# Memory.net
KiCad netlist of a schematic drawn in Altium Designer
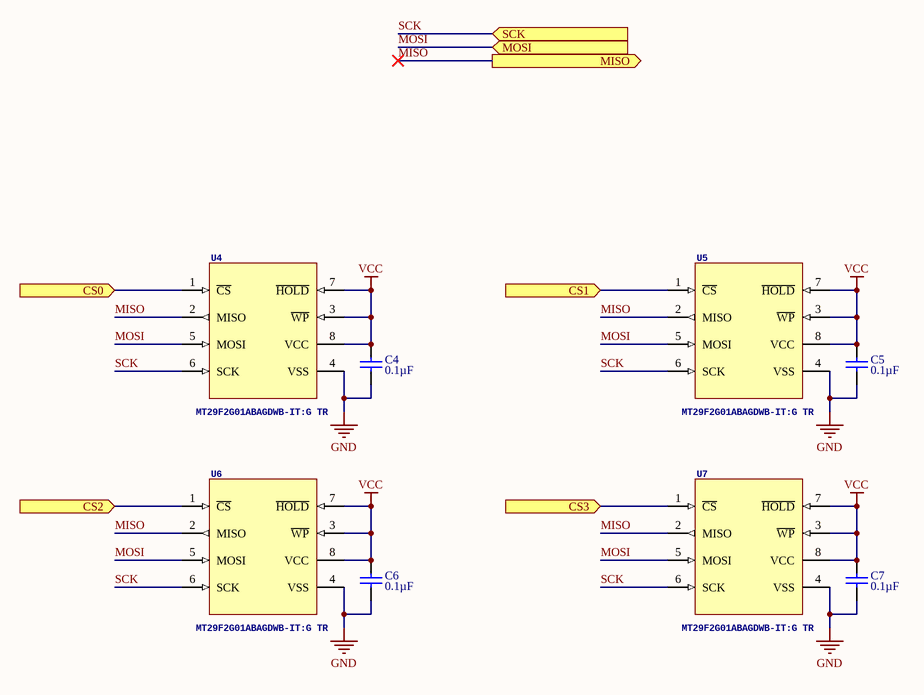
[diagram p0: Memory.SchDoc]

(export (version "E")
  (design (tool "Eeschema 10.0.6"))
  (components
    (comp (ref "C4")
      (value "CL10B104KO8NFNC")
      (footprint "C0603N")
      (fields
        (field (name "HOUSEPART") "NO")
        (field (name "TOLERANCE") "±10%")
        (field (name "VOLTAGE") "16V")
        (field (name "CAPACITANCE") "0.1µF")
      )
      (libsource (lib "MF_Passives") (part "CAPACITOR_NP"))
    )
    (comp (ref "C5")
      (value "CL10B104KO8NFNC")
      (footprint "C0603N")
      (fields
        (field (name "HOUSEPART") "NO")
        (field (name "TOLERANCE") "±10%")
        (field (name "VOLTAGE") "16V")
        (field (name "CAPACITANCE") "0.1µF")
      )
      (libsource (lib "MF_Passives") (part "CAPACITOR_NP"))
    )
    (comp (ref "C6")
      (value "CL10B104KO8NFNC")
      (footprint "C0603N")
      (fields
        (field (name "HOUSEPART") "NO")
        (field (name "TOLERANCE") "±10%")
        (field (name "VOLTAGE") "16V")
        (field (name "CAPACITANCE") "0.1µF")
      )
      (libsource (lib "MF_Passives") (part "CAPACITOR_NP"))
    )
    (comp (ref "C7")
      (value "CL10B104KO8NFNC")
      (footprint "C0603N")
      (fields
        (field (name "HOUSEPART") "NO")
        (field (name "TOLERANCE") "±10%")
        (field (name "VOLTAGE") "16V")
        (field (name "CAPACITANCE") "0.1µF")
      )
      (libsource (lib "MF_Passives") (part "CAPACITOR_NP"))
    )
    (comp (ref "U4")
      (value "MT29F2G01ABAGDWB-IT:G TR")
      (footprint "8-UDFN-MT29F")
      (description "IC Flash 2GB (UDFN8)")
      (libsource (lib "micron") (part "MT29F2G01ABAGDWB-IT{colon}G TR"))
    )
    (comp (ref "U5")
      (value "MT29F2G01ABAGDWB-IT:G TR")
      (footprint "8-UDFN-MT29F")
      (description "IC Flash 2GB (UDFN8)")
      (libsource (lib "micron") (part "MT29F2G01ABAGDWB-IT{colon}G TR"))
    )
    (comp (ref "U6")
      (value "MT29F2G01ABAGDWB-IT:G TR")
      (footprint "8-UDFN-MT29F")
      (description "IC Flash 2GB (UDFN8)")
      (libsource (lib "micron") (part "MT29F2G01ABAGDWB-IT{colon}G TR"))
    )
    (comp (ref "U7")
      (value "MT29F2G01ABAGDWB-IT:G TR")
      (footprint "8-UDFN-MT29F")
      (description "IC Flash 2GB (UDFN8)")
      (libsource (lib "micron") (part "MT29F2G01ABAGDWB-IT{colon}G TR"))
    )
  )
  (nets
    (net (code "1") (name "/CS0") (class "Default")
      (node (ref "U4") (pin "1") (pinfunction "~{CS}_1") (pintype "input"))
    )
    (net (code "2") (name "/CS1") (class "Default")
      (node (ref "U5") (pin "1") (pinfunction "~{CS}_1") (pintype "input"))
    )
    (net (code "3") (name "/CS2") (class "Default")
      (node (ref "U6") (pin "1") (pinfunction "~{CS}_1") (pintype "input"))
    )
    (net (code "4") (name "/CS3") (class "Default")
      (node (ref "U7") (pin "1") (pinfunction "~{CS}_1") (pintype "input"))
    )
    (net (code "5") (name "/MISO") (class "Default")
      (node (ref "U4") (pin "2") (pinfunction "MISO_2") (pintype "output"))
      (node (ref "U5") (pin "2") (pinfunction "MISO_2") (pintype "output"))
      (node (ref "U6") (pin "2") (pinfunction "MISO_2") (pintype "output"))
      (node (ref "U7") (pin "2") (pinfunction "MISO_2") (pintype "output"))
    )
    (net (code "6") (name "/MOSI") (class "Default")
      (node (ref "U4") (pin "5") (pinfunction "MOSI_5") (pintype "input"))
      (node (ref "U5") (pin "5") (pinfunction "MOSI_5") (pintype "input"))
      (node (ref "U6") (pin "5") (pinfunction "MOSI_5") (pintype "input"))
      (node (ref "U7") (pin "5") (pinfunction "MOSI_5") (pintype "input"))
    )
    (net (code "7") (name "/SCK") (class "Default")
      (node (ref "U4") (pin "6") (pinfunction "SCK_6") (pintype "input"))
      (node (ref "U5") (pin "6") (pinfunction "SCK_6") (pintype "input"))
      (node (ref "U6") (pin "6") (pinfunction "SCK_6") (pintype "input"))
      (node (ref "U7") (pin "6") (pinfunction "SCK_6") (pintype "input"))
    )
    (net (code "8") (name "GND") (class "Default")
      (node (ref "C4") (pin "2") (pinfunction "2_2") (pintype "passive"))
      (node (ref "C5") (pin "2") (pinfunction "2_2") (pintype "passive"))
      (node (ref "C6") (pin "2") (pinfunction "2_2") (pintype "passive"))
      (node (ref "C7") (pin "2") (pinfunction "2_2") (pintype "passive"))
      (node (ref "U4") (pin "4") (pinfunction "VSS_4") (pintype "power_in"))
      (node (ref "U5") (pin "4") (pinfunction "VSS_4") (pintype "power_in"))
      (node (ref "U6") (pin "4") (pinfunction "VSS_4") (pintype "power_in"))
      (node (ref "U7") (pin "4") (pinfunction "VSS_4") (pintype "power_in"))
    )
    (net (code "9") (name "VCC") (class "Default")
      (node (ref "C4") (pin "1") (pinfunction "1_1") (pintype "passive"))
      (node (ref "C5") (pin "1") (pinfunction "1_1") (pintype "passive"))
      (node (ref "C6") (pin "1") (pinfunction "1_1") (pintype "passive"))
      (node (ref "C7") (pin "1") (pinfunction "1_1") (pintype "passive"))
      (node (ref "U4") (pin "3") (pinfunction "~{WP}_3") (pintype "input"))
      (node (ref "U4") (pin "7") (pinfunction "~{HOLD}_7") (pintype "input"))
      (node (ref "U4") (pin "8") (pinfunction "VCC_8") (pintype "power_in"))
      (node (ref "U5") (pin "3") (pinfunction "~{WP}_3") (pintype "input"))
      (node (ref "U5") (pin "7") (pinfunction "~{HOLD}_7") (pintype "input"))
      (node (ref "U5") (pin "8") (pinfunction "VCC_8") (pintype "power_in"))
      (node (ref "U6") (pin "3") (pinfunction "~{WP}_3") (pintype "input"))
      (node (ref "U6") (pin "7") (pinfunction "~{HOLD}_7") (pintype "input"))
      (node (ref "U6") (pin "8") (pinfunction "VCC_8") (pintype "power_in"))
      (node (ref "U7") (pin "3") (pinfunction "~{WP}_3") (pintype "input"))
      (node (ref "U7") (pin "7") (pinfunction "~{HOLD}_7") (pintype "input"))
      (node (ref "U7") (pin "8") (pinfunction "VCC_8") (pintype "power_in"))
    )
  )
)
